# Xenium2019.net
KiCad netlist of a schematic drawn in EAGLE
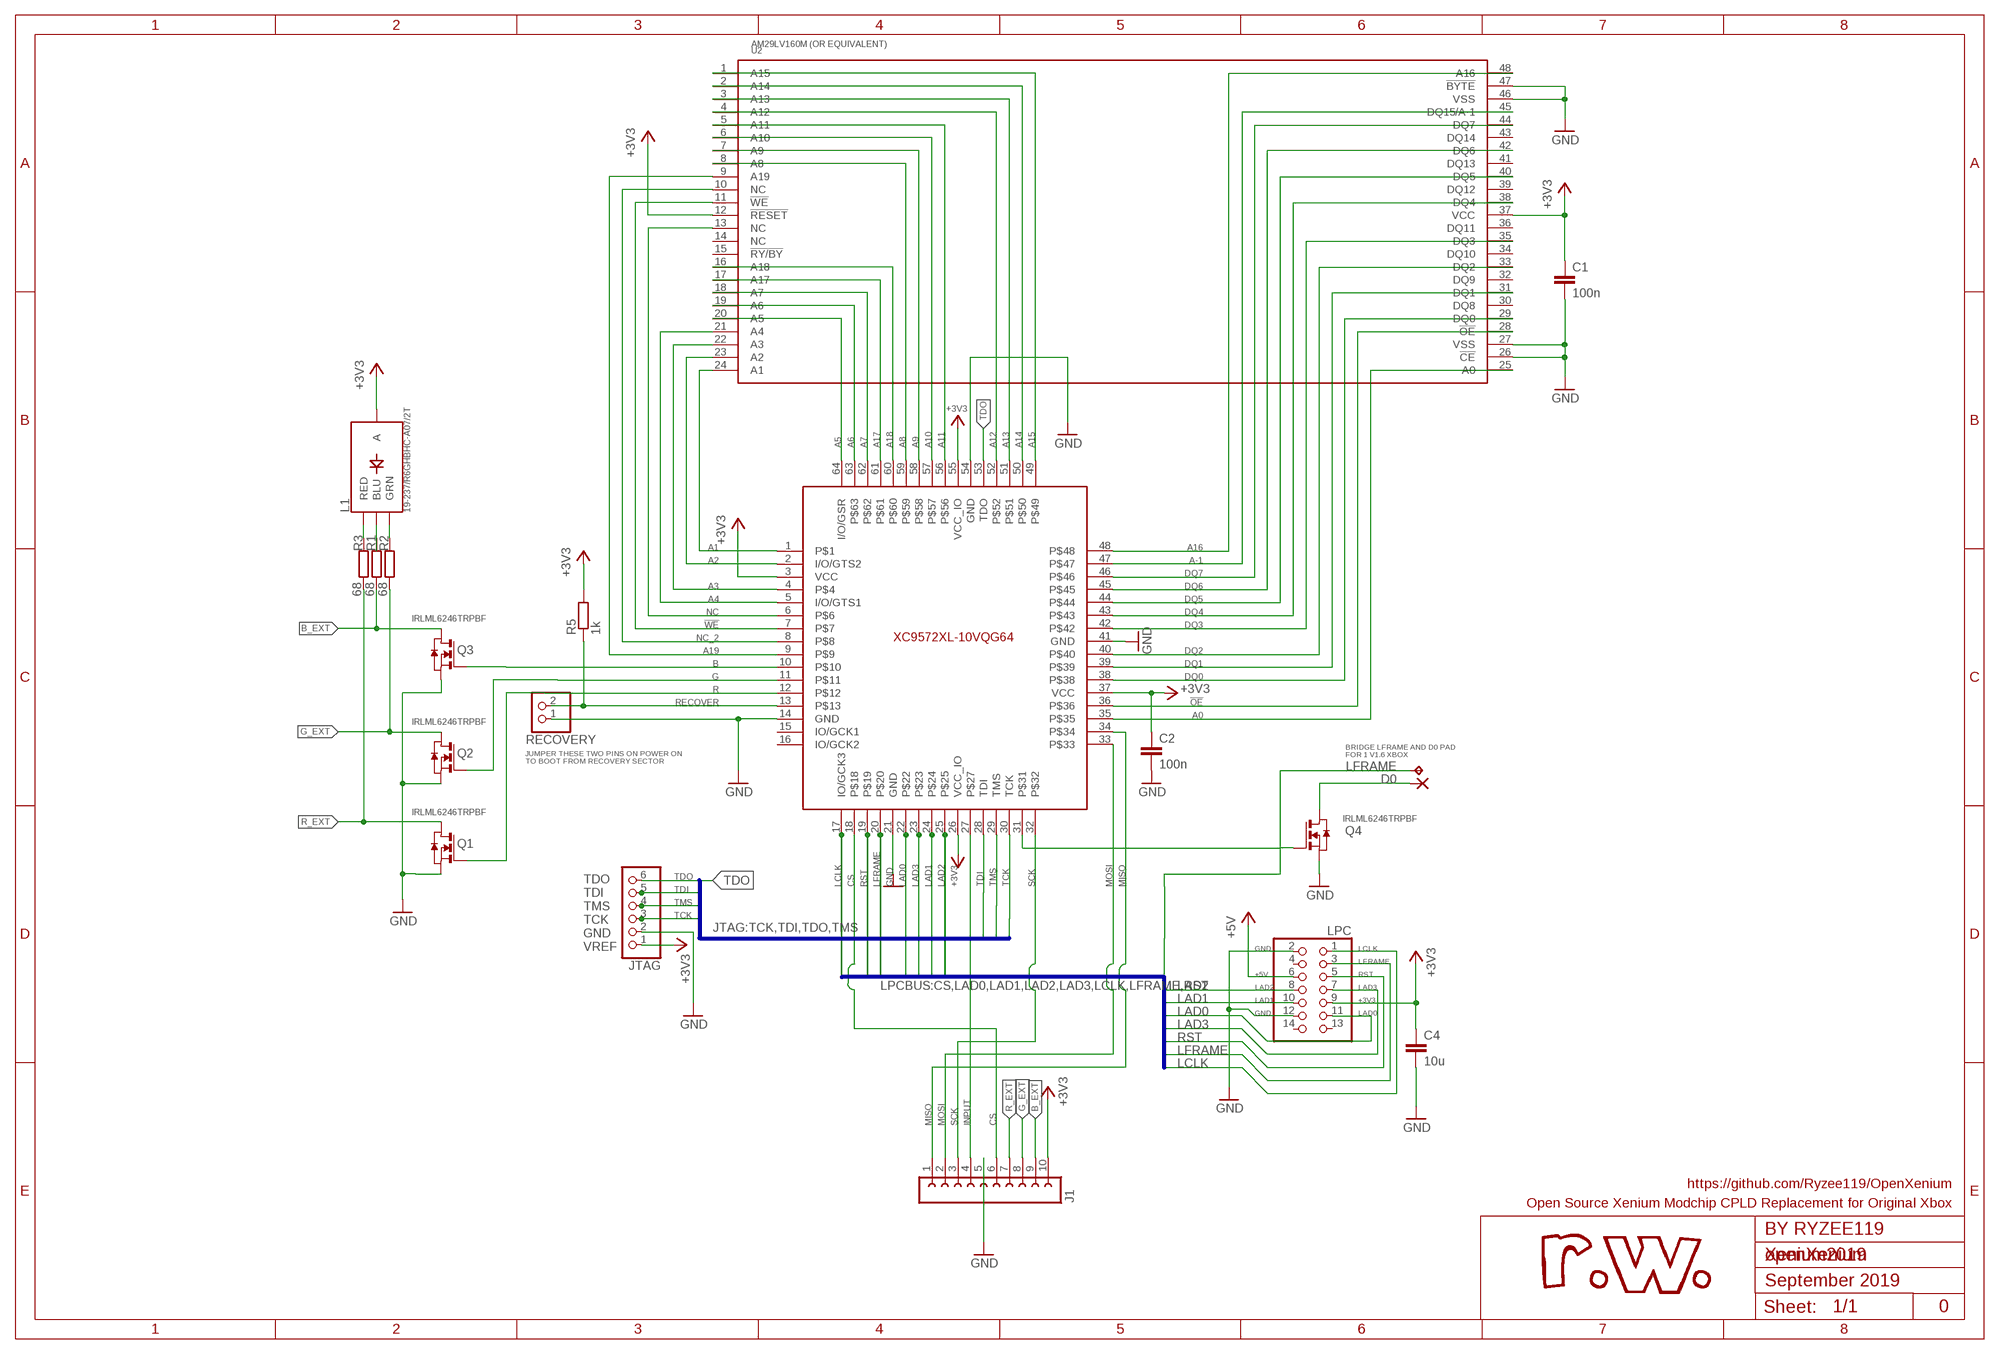
[diagram p0: schematic, sheet 1]

(export (version "E")
  (design (tool "Eeschema 10.0.6"))
  (components
    (comp (ref "C1")
      (value "100n")
      (footprint "eagle-import:C0603")
      (libsource (lib "eagle-import") (part "C-EUC0603"))
    )
    (comp (ref "C2")
      (value "100n")
      (footprint "eagle-import:C0603")
      (libsource (lib "eagle-import") (part "C-EUC0603"))
    )
    (comp (ref "C4")
      (value "10u")
      (footprint "eagle-import:C0603")
      (libsource (lib "eagle-import") (part "C-EUC0603"))
    )
    (comp (ref "D0")
      (value "SMD2")
      (footprint "eagle-import:SMD1,27-2,54")
      (libsource (lib "eagle-import") (part "SMD2"))
    )
    (comp (ref "J1")
      (value "FE10-1")
      (footprint "eagle-import:FE10")
      (libsource (lib "eagle-import") (part "FE10-1"))
    )
    (comp (ref "JTAG")
      (value "PINHD-1X6")
      (footprint "eagle-import:1X06")
      (libsource (lib "eagle-import") (part "PINHD-1X6"))
    )
    (comp (ref "L1")
      (value "19-237/R6GHBHC-A07/2T")
      (footprint "eagle-import:4-SMD-R6GHBHC")
      (libsource (lib "eagle-import") (part "19-237/R6GHBHC-A07/2T"))
    )
    (comp (ref "LPC")
      (value "PINHD-2X7")
      (footprint "eagle-import:2X07")
      (libsource (lib "eagle-import") (part "PINHD-2X7"))
    )
    (comp (ref "Q1")
      (value "310mA/60V/1.6Ω")
      (footprint "eagle-import:SOT-23")
      (libsource (lib "eagle-import") (part "NMOSSOT23"))
    )
    (comp (ref "Q2")
      (value "310mA/60V/1.6Ω")
      (footprint "eagle-import:SOT-23")
      (libsource (lib "eagle-import") (part "NMOSSOT23"))
    )
    (comp (ref "Q3")
      (value "310mA/60V/1.6Ω")
      (footprint "eagle-import:SOT-23")
      (libsource (lib "eagle-import") (part "NMOSSOT23"))
    )
    (comp (ref "Q4")
      (value "310mA/60V/1.6Ω")
      (footprint "eagle-import:SOT-23")
      (libsource (lib "eagle-import") (part "NMOSSOT23"))
    )
    (comp (ref "R1")
      (value "68")
      (footprint "eagle-import:R0603")
      (libsource (lib "eagle-import") (part "R-EU_R0603"))
    )
    (comp (ref "R2")
      (value "68")
      (footprint "eagle-import:R0603")
      (libsource (lib "eagle-import") (part "R-EU_R0603"))
    )
    (comp (ref "R3")
      (value "68")
      (footprint "eagle-import:R0603")
      (libsource (lib "eagle-import") (part "R-EU_R0603"))
    )
    (comp (ref "R5")
      (value "1k")
      (footprint "eagle-import:R0603")
      (libsource (lib "eagle-import") (part "R-EU_R0603"))
    )
    (comp (ref "RECOVERY")
      (value "PINHD-1X2")
      (footprint "eagle-import:1X02")
      (libsource (lib "eagle-import") (part "PINHD-1X2"))
    )
    (comp (ref "TP1")
      (value "TPTP13SQ")
      (footprint "eagle-import:TP13SQ")
      (libsource (lib "eagle-import") (part "TPTP13SQ"))
    )
    (comp (ref "U1")
      (value "XC9572XL-10VQG64")
      (footprint "eagle-import:LQFP64")
      (libsource (lib "eagle-import") (part "XC9572XL-10VQG64"))
    )
    (comp (ref "U2")
      (value "AM29LV160M")
      (footprint "eagle-import:TSOP48")
      (libsource (lib "eagle-import") (part "AM29LV160M"))
    )
  )
  (nets
    (net (code "3") (name "+3V3") (class "Default")
      (node (ref "C1") (pin "1") (pinfunction "1_1") (pintype "passive"))
      (node (ref "C2") (pin "1") (pinfunction "1_1") (pintype "passive"))
      (node (ref "C4") (pin "1") (pinfunction "1_1") (pintype "passive"))
      (node (ref "J1") (pin "10") (pinfunction "10_10") (pintype "passive"))
      (node (ref "JTAG") (pin "1") (pinfunction "1_1") (pintype "passive"))
      (node (ref "L1") (pin "P$2") (pinfunction "A_P$2") (pintype "bidirectional"))
      (node (ref "LPC") (pin "9") (pinfunction "9_9") (pintype "passive"))
      (node (ref "R5") (pin "2") (pinfunction "2_2") (pintype "passive"))
      (node (ref "U1") (pin "26") (pinfunction "VCC_IO_26") (pintype "bidirectional"))
      (node (ref "U1") (pin "3") (pinfunction "VCC_3") (pintype "bidirectional"))
      (node (ref "U1") (pin "37") (pinfunction "VCC_37") (pintype "bidirectional"))
      (node (ref "U1") (pin "55") (pinfunction "VCC_IO_55") (pintype "bidirectional"))
      (node (ref "U2") (pin "12") (pinfunction "~{RESET}_12") (pintype "bidirectional"))
      (node (ref "U2") (pin "37") (pinfunction "VCC_37") (pintype "bidirectional"))
    )
    (net (code "4") (name "+5V") (class "Default")
      (node (ref "LPC") (pin "6") (pinfunction "6_6") (pintype "passive"))
    )
    (net (code "5") (name "/A-1") (class "Default")
      (node (ref "U1") (pin "47") (pinfunction "P$47_47") (pintype "bidirectional"))
      (node (ref "U2") (pin "45") (pinfunction "DQ15/A-1_45") (pintype "bidirectional"))
    )
    (net (code "6") (name "/A0") (class "Default")
      (node (ref "U1") (pin "35") (pinfunction "P$35_35") (pintype "bidirectional"))
      (node (ref "U2") (pin "25") (pinfunction "A0_25") (pintype "bidirectional"))
    )
    (net (code "7") (name "/A1") (class "Default")
      (node (ref "U1") (pin "1") (pinfunction "P$1_1") (pintype "bidirectional"))
      (node (ref "U2") (pin "24") (pinfunction "A1_24") (pintype "bidirectional"))
    )
    (net (code "8") (name "/A2") (class "Default")
      (node (ref "U1") (pin "2") (pinfunction "I/O/GTS2_2") (pintype "bidirectional"))
      (node (ref "U2") (pin "23") (pinfunction "A2_23") (pintype "bidirectional"))
    )
    (net (code "9") (name "/A3") (class "Default")
      (node (ref "U1") (pin "4") (pinfunction "P$4_4") (pintype "bidirectional"))
      (node (ref "U2") (pin "22") (pinfunction "A3_22") (pintype "bidirectional"))
    )
    (net (code "10") (name "/A4") (class "Default")
      (node (ref "U1") (pin "5") (pinfunction "I/O/GTS1_5") (pintype "bidirectional"))
      (node (ref "U2") (pin "21") (pinfunction "A4_21") (pintype "bidirectional"))
    )
    (net (code "11") (name "/A5") (class "Default")
      (node (ref "U1") (pin "64") (pinfunction "I/O/GSR_64") (pintype "bidirectional"))
      (node (ref "U2") (pin "20") (pinfunction "A5_20") (pintype "bidirectional"))
    )
    (net (code "12") (name "/A6") (class "Default")
      (node (ref "U1") (pin "63") (pinfunction "P$63_63") (pintype "bidirectional"))
      (node (ref "U2") (pin "19") (pinfunction "A6_19") (pintype "bidirectional"))
    )
    (net (code "13") (name "/A7") (class "Default")
      (node (ref "U1") (pin "62") (pinfunction "P$62_62") (pintype "bidirectional"))
      (node (ref "U2") (pin "18") (pinfunction "A7_18") (pintype "bidirectional"))
    )
    (net (code "14") (name "/A8") (class "Default")
      (node (ref "U1") (pin "59") (pinfunction "P$59_59") (pintype "bidirectional"))
      (node (ref "U2") (pin "8") (pinfunction "A8_8") (pintype "bidirectional"))
    )
    (net (code "15") (name "/A9") (class "Default")
      (node (ref "U1") (pin "58") (pinfunction "P$58_58") (pintype "bidirectional"))
      (node (ref "U2") (pin "7") (pinfunction "A9_7") (pintype "bidirectional"))
    )
    (net (code "16") (name "/A10") (class "Default")
      (node (ref "U1") (pin "57") (pinfunction "P$57_57") (pintype "bidirectional"))
      (node (ref "U2") (pin "6") (pinfunction "A10_6") (pintype "bidirectional"))
    )
    (net (code "17") (name "/A11") (class "Default")
      (node (ref "U1") (pin "56") (pinfunction "P$56_56") (pintype "bidirectional"))
      (node (ref "U2") (pin "5") (pinfunction "A11_5") (pintype "bidirectional"))
    )
    (net (code "18") (name "/A12") (class "Default")
      (node (ref "U1") (pin "52") (pinfunction "P$52_52") (pintype "bidirectional"))
      (node (ref "U2") (pin "4") (pinfunction "A12_4") (pintype "bidirectional"))
    )
    (net (code "19") (name "/A13") (class "Default")
      (node (ref "U1") (pin "51") (pinfunction "P$51_51") (pintype "bidirectional"))
      (node (ref "U2") (pin "3") (pinfunction "A13_3") (pintype "bidirectional"))
    )
    (net (code "20") (name "/A14") (class "Default")
      (node (ref "U1") (pin "50") (pinfunction "P$50_50") (pintype "bidirectional"))
      (node (ref "U2") (pin "2") (pinfunction "A14_2") (pintype "bidirectional"))
    )
    (net (code "21") (name "/A15") (class "Default")
      (node (ref "U1") (pin "49") (pinfunction "P$49_49") (pintype "bidirectional"))
      (node (ref "U2") (pin "1") (pinfunction "A15_1") (pintype "bidirectional"))
    )
    (net (code "22") (name "/A16") (class "Default")
      (node (ref "U1") (pin "48") (pinfunction "P$48_48") (pintype "bidirectional"))
      (node (ref "U2") (pin "48") (pinfunction "A16_48") (pintype "bidirectional"))
    )
    (net (code "23") (name "/A17") (class "Default")
      (node (ref "U1") (pin "61") (pinfunction "P$61_61") (pintype "bidirectional"))
      (node (ref "U2") (pin "17") (pinfunction "A17_17") (pintype "bidirectional"))
    )
    (net (code "24") (name "/A18") (class "Default")
      (node (ref "U1") (pin "60") (pinfunction "P$60_60") (pintype "bidirectional"))
      (node (ref "U2") (pin "16") (pinfunction "A18_16") (pintype "bidirectional"))
    )
    (net (code "25") (name "/A19") (class "Default")
      (node (ref "U1") (pin "9") (pinfunction "P$9_9") (pintype "bidirectional"))
      (node (ref "U2") (pin "9") (pinfunction "A19_9") (pintype "bidirectional"))
    )
    (net (code "26") (name "/B") (class "Default")
      (node (ref "Q3") (pin "3") (pinfunction "G_3") (pintype "passive"))
      (node (ref "U1") (pin "10") (pinfunction "P$10_10") (pintype "bidirectional"))
    )
    (net (code "27") (name "/CS") (class "Default")
      (node (ref "J1") (pin "6") (pinfunction "6_6") (pintype "passive"))
      (node (ref "U1") (pin "18") (pinfunction "P$18_18") (pintype "bidirectional"))
    )
    (net (code "28") (name "/DQ0") (class "Default")
      (node (ref "U1") (pin "38") (pinfunction "P$38_38") (pintype "bidirectional"))
      (node (ref "U2") (pin "29") (pinfunction "DQ0_29") (pintype "bidirectional"))
    )
    (net (code "29") (name "/DQ1") (class "Default")
      (node (ref "U1") (pin "39") (pinfunction "P$39_39") (pintype "bidirectional"))
      (node (ref "U2") (pin "31") (pinfunction "DQ1_31") (pintype "bidirectional"))
    )
    (net (code "30") (name "/DQ2") (class "Default")
      (node (ref "U1") (pin "40") (pinfunction "P$40_40") (pintype "bidirectional"))
      (node (ref "U2") (pin "33") (pinfunction "DQ2_33") (pintype "bidirectional"))
    )
    (net (code "31") (name "/DQ3") (class "Default")
      (node (ref "U1") (pin "42") (pinfunction "P$42_42") (pintype "bidirectional"))
      (node (ref "U2") (pin "35") (pinfunction "DQ3_35") (pintype "bidirectional"))
    )
    (net (code "32") (name "/DQ4") (class "Default")
      (node (ref "U1") (pin "43") (pinfunction "P$43_43") (pintype "bidirectional"))
      (node (ref "U2") (pin "38") (pinfunction "DQ4_38") (pintype "bidirectional"))
    )
    (net (code "33") (name "/DQ5") (class "Default")
      (node (ref "U1") (pin "44") (pinfunction "P$44_44") (pintype "bidirectional"))
      (node (ref "U2") (pin "40") (pinfunction "DQ5_40") (pintype "bidirectional"))
    )
    (net (code "34") (name "/DQ6") (class "Default")
      (node (ref "U1") (pin "45") (pinfunction "P$45_45") (pintype "bidirectional"))
      (node (ref "U2") (pin "42") (pinfunction "DQ6_42") (pintype "bidirectional"))
    )
    (net (code "35") (name "/DQ7") (class "Default")
      (node (ref "U1") (pin "46") (pinfunction "P$46_46") (pintype "bidirectional"))
      (node (ref "U2") (pin "44") (pinfunction "DQ7_44") (pintype "bidirectional"))
    )
    (net (code "36") (name "/G") (class "Default")
      (node (ref "Q2") (pin "3") (pinfunction "G_3") (pintype "passive"))
      (node (ref "U1") (pin "11") (pinfunction "P$11_11") (pintype "bidirectional"))
    )
    (net (code "37") (name "/INPUT") (class "Default")
      (node (ref "J1") (pin "4") (pinfunction "4_4") (pintype "passive"))
      (node (ref "U1") (pin "27") (pinfunction "P$27_27") (pintype "bidirectional"))
    )
    (net (code "38") (name "/LAD0") (class "Default")
      (node (ref "LPC") (pin "11") (pinfunction "11_11") (pintype "passive"))
      (node (ref "U1") (pin "22") (pinfunction "P$22_22") (pintype "bidirectional"))
    )
    (net (code "39") (name "/LAD1") (class "Default")
      (node (ref "LPC") (pin "10") (pinfunction "10_10") (pintype "passive"))
      (node (ref "U1") (pin "24") (pinfunction "P$24_24") (pintype "bidirectional"))
    )
    (net (code "40") (name "/LAD2") (class "Default")
      (node (ref "LPC") (pin "8") (pinfunction "8_8") (pintype "passive"))
      (node (ref "U1") (pin "25") (pinfunction "P$25_25") (pintype "bidirectional"))
    )
    (net (code "41") (name "/LAD3") (class "Default")
      (node (ref "LPC") (pin "7") (pinfunction "7_7") (pintype "passive"))
      (node (ref "U1") (pin "23") (pinfunction "P$23_23") (pintype "bidirectional"))
    )
    (net (code "42") (name "/LCLK") (class "Default")
      (node (ref "LPC") (pin "1") (pinfunction "1_1") (pintype "passive"))
      (node (ref "U1") (pin "17") (pinfunction "IO/GCK3_17") (pintype "bidirectional"))
    )
    (net (code "43") (name "/LFRAME") (class "Default")
      (node (ref "LPC") (pin "3") (pinfunction "3_3") (pintype "passive"))
      (node (ref "TP1") (pin "TP") (pinfunction "TP_TP") (pintype "input"))
      (node (ref "U1") (pin "20") (pinfunction "P$20_20") (pintype "bidirectional"))
    )
    (net (code "44") (name "/MISO") (class "Default")
      (node (ref "J1") (pin "1") (pinfunction "1_1") (pintype "passive"))
      (node (ref "U1") (pin "34") (pinfunction "P$34_34") (pintype "bidirectional"))
    )
    (net (code "45") (name "/MOSI") (class "Default")
      (node (ref "J1") (pin "2") (pinfunction "2_2") (pintype "passive"))
      (node (ref "U1") (pin "33") (pinfunction "P$33_33") (pintype "bidirectional"))
    )
    (net (code "46") (name "/NC") (class "Default")
      (node (ref "U1") (pin "6") (pinfunction "P$6_6") (pintype "bidirectional"))
      (node (ref "U2") (pin "13") (pinfunction "NC_13") (pintype "bidirectional"))
    )
    (net (code "47") (name "/NC_2") (class "Default")
      (node (ref "U1") (pin "8") (pinfunction "P$8_8") (pintype "bidirectional"))
      (node (ref "U2") (pin "10") (pinfunction "NC_10") (pintype "bidirectional"))
    )
    (net (code "48") (name "/R") (class "Default")
      (node (ref "Q1") (pin "3") (pinfunction "G_3") (pintype "passive"))
      (node (ref "U1") (pin "12") (pinfunction "P$12_12") (pintype "bidirectional"))
    )
    (net (code "49") (name "/RECOVER") (class "Default")
      (node (ref "R5") (pin "1") (pinfunction "1_1") (pintype "passive"))
      (node (ref "RECOVERY") (pin "2") (pinfunction "2_2") (pintype "passive"))
      (node (ref "U1") (pin "13") (pinfunction "P$13_13") (pintype "bidirectional"))
    )
    (net (code "50") (name "/RST") (class "Default")
      (node (ref "LPC") (pin "5") (pinfunction "5_5") (pintype "passive"))
      (node (ref "U1") (pin "19") (pinfunction "P$19_19") (pintype "bidirectional"))
    )
    (net (code "51") (name "/SCK") (class "Default")
      (node (ref "J1") (pin "3") (pinfunction "3_3") (pintype "passive"))
      (node (ref "U1") (pin "32") (pinfunction "P$32_32") (pintype "bidirectional"))
    )
    (net (code "52") (name "/TCK") (class "Default")
      (node (ref "JTAG") (pin "3") (pinfunction "3_3") (pintype "passive"))
      (node (ref "U1") (pin "30") (pinfunction "TCK_30") (pintype "bidirectional"))
    )
    (net (code "53") (name "/TDI") (class "Default")
      (node (ref "JTAG") (pin "5") (pinfunction "5_5") (pintype "passive"))
      (node (ref "U1") (pin "28") (pinfunction "TDI_28") (pintype "bidirectional"))
    )
    (net (code "54") (name "/TMS") (class "Default")
      (node (ref "JTAG") (pin "4") (pinfunction "4_4") (pintype "passive"))
      (node (ref "U1") (pin "29") (pinfunction "TMS_29") (pintype "bidirectional"))
    )
    (net (code "57") (name "/~{OE}") (class "Default")
      (node (ref "U1") (pin "36") (pinfunction "P$36_36") (pintype "bidirectional"))
      (node (ref "U2") (pin "28") (pinfunction "~{OE}_28") (pintype "bidirectional"))
    )
    (net (code "58") (name "/~{WE}") (class "Default")
      (node (ref "U1") (pin "7") (pinfunction "P$7_7") (pintype "bidirectional"))
      (node (ref "U2") (pin "11") (pinfunction "~{WE}_11") (pintype "bidirectional"))
    )
    (net (code "59") (name "B_EXT") (class "Default")
      (node (ref "J1") (pin "9") (pinfunction "9_9") (pintype "passive"))
      (node (ref "Q3") (pin "1") (pinfunction "D_1") (pintype "passive"))
      (node (ref "R1") (pin "2") (pinfunction "2_2") (pintype "passive"))
    )
    (net (code "60") (name "GND") (class "Default")
      (node (ref "C1") (pin "2") (pinfunction "2_2") (pintype "passive"))
      (node (ref "C2") (pin "2") (pinfunction "2_2") (pintype "passive"))
      (node (ref "C4") (pin "2") (pinfunction "2_2") (pintype "passive"))
      (node (ref "J1") (pin "5") (pinfunction "5_5") (pintype "passive"))
      (node (ref "JTAG") (pin "2") (pinfunction "2_2") (pintype "passive"))
      (node (ref "LPC") (pin "12") (pinfunction "12_12") (pintype "passive"))
      (node (ref "LPC") (pin "2") (pinfunction "2_2") (pintype "passive"))
      (node (ref "Q1") (pin "2") (pinfunction "S_2") (pintype "passive"))
      (node (ref "Q2") (pin "2") (pinfunction "S_2") (pintype "passive"))
      (node (ref "Q3") (pin "2") (pinfunction "S_2") (pintype "passive"))
      (node (ref "Q4") (pin "2") (pinfunction "S_2") (pintype "passive"))
      (node (ref "RECOVERY") (pin "1") (pinfunction "1_1") (pintype "passive"))
      (node (ref "U1") (pin "14") (pinfunction "GND_14") (pintype "bidirectional"))
      (node (ref "U1") (pin "21") (pinfunction "GND_21") (pintype "bidirectional"))
      (node (ref "U1") (pin "41") (pinfunction "GND_41") (pintype "bidirectional"))
      (node (ref "U1") (pin "54") (pinfunction "GND_54") (pintype "bidirectional"))
      (node (ref "U2") (pin "26") (pinfunction "~{CE}_26") (pintype "bidirectional"))
      (node (ref "U2") (pin "27") (pinfunction "VSS_27") (pintype "bidirectional"))
      (node (ref "U2") (pin "46") (pinfunction "VSS_46") (pintype "bidirectional"))
      (node (ref "U2") (pin "47") (pinfunction "~{BYTE}_47") (pintype "bidirectional"))
    )
    (net (code "61") (name "G_EXT") (class "Default")
      (node (ref "J1") (pin "8") (pinfunction "8_8") (pintype "passive"))
      (node (ref "Q2") (pin "1") (pinfunction "D_1") (pintype "passive"))
      (node (ref "R2") (pin "2") (pinfunction "2_2") (pintype "passive"))
    )
    (net (code "62") (name "Net-(D0-P)") (class "Default")
      (node (ref "D0") (pin "1") (pinfunction "P_1") (pintype "passive"))
      (node (ref "Q4") (pin "1") (pinfunction "D_1") (pintype "passive"))
    )
    (net (code "63") (name "Net-(L1-BLU)") (class "Default")
      (node (ref "L1") (pin "P$4") (pinfunction "BLU_P$4") (pintype "bidirectional"))
      (node (ref "R1") (pin "1") (pinfunction "1_1") (pintype "passive"))
    )
    (net (code "64") (name "Net-(L1-GRN)") (class "Default")
      (node (ref "L1") (pin "P$3") (pinfunction "GRN_P$3") (pintype "bidirectional"))
      (node (ref "R2") (pin "1") (pinfunction "1_1") (pintype "passive"))
    )
    (net (code "65") (name "Net-(L1-RED)") (class "Default")
      (node (ref "L1") (pin "P$1") (pinfunction "RED_P$1") (pintype "bidirectional"))
      (node (ref "R3") (pin "1") (pinfunction "1_1") (pintype "passive"))
    )
    (net (code "66") (name "Net-(Q4-G)") (class "Default")
      (node (ref "Q4") (pin "3") (pinfunction "G_3") (pintype "passive"))
      (node (ref "U1") (pin "31") (pinfunction "P$31_31") (pintype "bidirectional"))
    )
    (net (code "67") (name "R_EXT") (class "Default")
      (node (ref "J1") (pin "7") (pinfunction "7_7") (pintype "passive"))
      (node (ref "Q1") (pin "1") (pinfunction "D_1") (pintype "passive"))
      (node (ref "R3") (pin "2") (pinfunction "2_2") (pintype "passive"))
    )
    (net (code "68") (name "TDO") (class "Default")
      (node (ref "JTAG") (pin "6") (pinfunction "6_6") (pintype "passive"))
      (node (ref "U1") (pin "53") (pinfunction "TDO_53") (pintype "bidirectional"))
    )
    (net (code "69") (name "unconnected-(LPC-Pad4)") (class "Default")
      (node (ref "LPC") (pin "4") (pinfunction "4_4") (pintype "passive"))
    )
    (net (code "70") (name "unconnected-(LPC-Pad13)") (class "Default")
      (node (ref "LPC") (pin "13") (pinfunction "13_13") (pintype "passive"))
    )
    (net (code "71") (name "unconnected-(LPC-Pad14)") (class "Default")
      (node (ref "LPC") (pin "14") (pinfunction "14_14") (pintype "passive"))
    )
    (net (code "72") (name "unconnected-(U1-IO{slash}GCK1-Pad15)") (class "Default")
      (node (ref "U1") (pin "15") (pinfunction "IO/GCK1_15") (pintype "bidirectional"))
    )
    (net (code "73") (name "unconnected-(U1-IO{slash}GCK2-Pad16)") (class "Default")
      (node (ref "U1") (pin "16") (pinfunction "IO/GCK2_16") (pintype "bidirectional"))
    )
    (net (code "74") (name "unconnected-(U2-DQ8-Pad30)") (class "Default")
      (node (ref "U2") (pin "30") (pinfunction "DQ8_30") (pintype "bidirectional"))
    )
    (net (code "75") (name "unconnected-(U2-DQ9-Pad32)") (class "Default")
      (node (ref "U2") (pin "32") (pinfunction "DQ9_32") (pintype "bidirectional"))
    )
    (net (code "76") (name "unconnected-(U2-DQ10-Pad34)") (class "Default")
      (node (ref "U2") (pin "34") (pinfunction "DQ10_34") (pintype "bidirectional"))
    )
    (net (code "77") (name "unconnected-(U2-DQ11-Pad36)") (class "Default")
      (node (ref "U2") (pin "36") (pinfunction "DQ11_36") (pintype "bidirectional"))
    )
    (net (code "78") (name "unconnected-(U2-DQ12-Pad39)") (class "Default")
      (node (ref "U2") (pin "39") (pinfunction "DQ12_39") (pintype "bidirectional"))
    )
    (net (code "79") (name "unconnected-(U2-DQ13-Pad41)") (class "Default")
      (node (ref "U2") (pin "41") (pinfunction "DQ13_41") (pintype "bidirectional"))
    )
    (net (code "80") (name "unconnected-(U2-DQ14-Pad43)") (class "Default")
      (node (ref "U2") (pin "43") (pinfunction "DQ14_43") (pintype "bidirectional"))
    )
    (net (code "81") (name "unconnected-(U2-NC-Pad14)") (class "Default")
      (node (ref "U2") (pin "14") (pinfunction "NC_14") (pintype "bidirectional"))
    )
    (net (code "82") (name "unconnected-(U2-~{RY{slash}BY}-Pad15)") (class "Default")
      (node (ref "U2") (pin "15") (pinfunction "~{RY/BY}_15") (pintype "bidirectional"))
    )
  )
)
